# Arduino_Nanolu_Kart_2.net
KiCad netlist of a schematic drawn in EAGLE
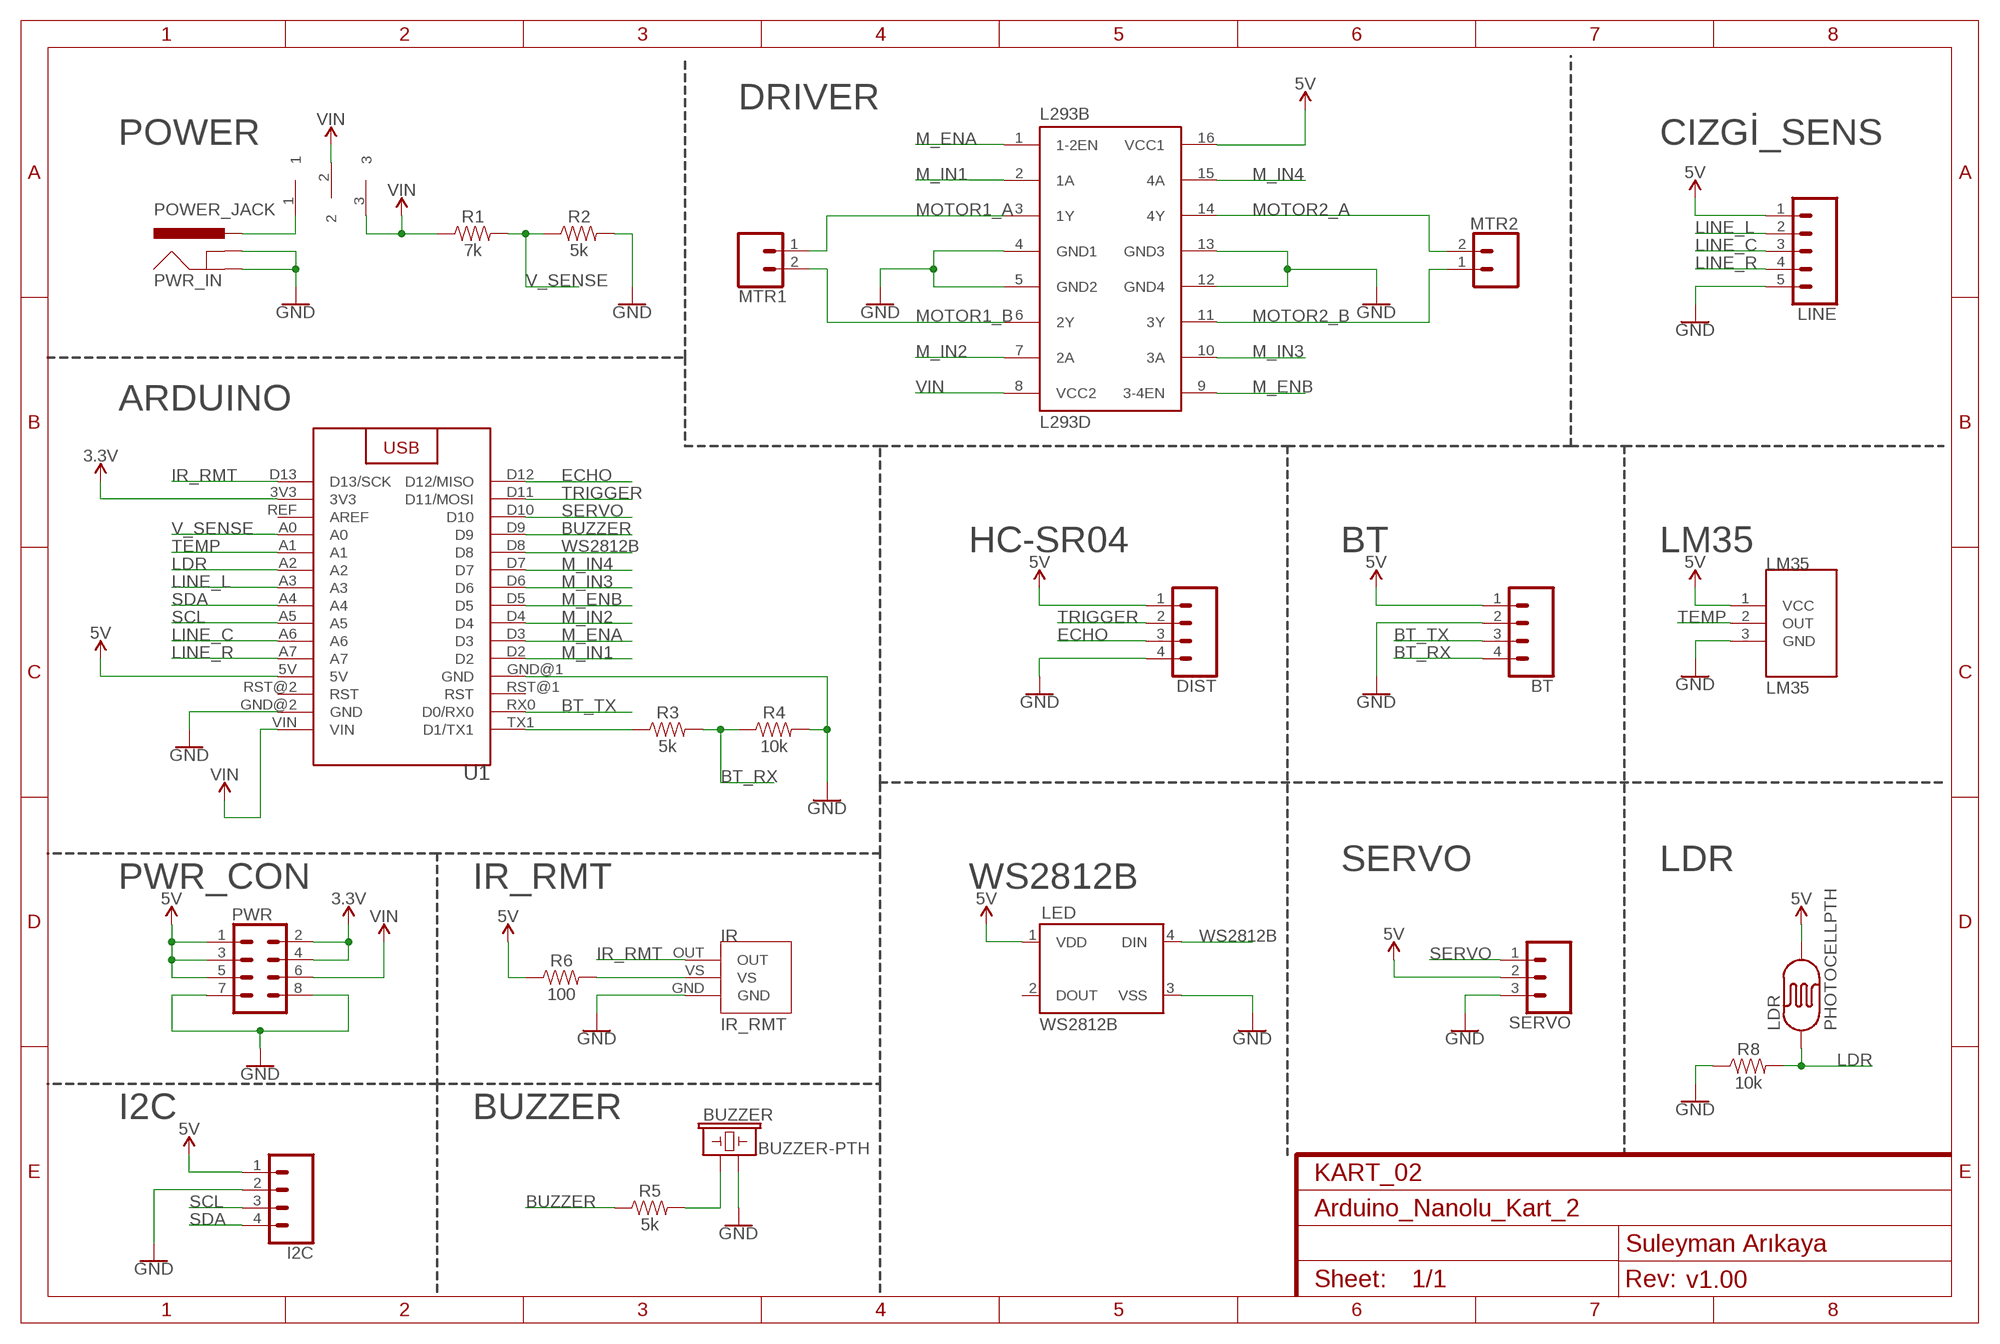
[diagram p0: schematic, sheet 1]

(export (version "E")
  (design (tool "Eeschema 10.0.6"))
  (components
    (comp (ref "BT")
      (value "CONN_04")
      (footprint "eagle-import:1X04")
      (libsource (lib "eagle-import") (part "CONN_04"))
    )
    (comp (ref "BUZZER")
      (value "BUZZER-PTH")
      (footprint "eagle-import:BUZZER-12MM")
      (libsource (lib "eagle-import") (part "BUZZER-PTH"))
    )
    (comp (ref "DIST")
      (value "CONN_04")
      (footprint "eagle-import:1X04")
      (libsource (lib "eagle-import") (part "CONN_04"))
    )
    (comp (ref "I2C")
      (value "CONN_04")
      (footprint "eagle-import:1X04")
      (libsource (lib "eagle-import") (part "CONN_04"))
    )
    (comp (ref "IR")
      (value "IR_RMT")
      (footprint "eagle-import:IR_SENSOR")
      (libsource (lib "eagle-import") (part "IR_SENSOR"))
    )
    (comp (ref "L293B")
      (value "L293D")
      (footprint "eagle-import:DIL16")
      (libsource (lib "eagle-import") (part "L293D"))
    )
    (comp (ref "LDR")
      (value "PHOTOCELLPTH")
      (footprint "eagle-import:PHOTOCELL")
      (libsource (lib "eagle-import") (part "PHOTOCELLPTH"))
    )
    (comp (ref "LED")
      (value "WS2812B")
      (footprint "eagle-import:WS2812B")
      (libsource (lib "eagle-import") (part "WS2812B"))
    )
    (comp (ref "LINE")
      (value "CONN_05")
      (footprint "eagle-import:1X05")
      (libsource (lib "eagle-import") (part "CONN_05"))
    )
    (comp (ref "LM35")
      (value "LM35")
      (footprint "eagle-import:TO-92")
      (fields (field (name "SPICEPREFIX") "U"))
      (libsource (lib "eagle-import") (part "LM35"))
    )
    (comp (ref "MTR1")
      (value "CONN_023.5MM")
      (footprint "eagle-import:SCREWTERMINAL-3.5MM-2")
      (libsource (lib "eagle-import") (part "CONN_023.5MM"))
    )
    (comp (ref "MTR2")
      (value "CONN_023.5MM")
      (footprint "eagle-import:SCREWTERMINAL-3.5MM-2")
      (libsource (lib "eagle-import") (part "CONN_023.5MM"))
    )
    (comp (ref "PWR")
      (value "CONN_04X2")
      (footprint "eagle-import:2X4")
      (libsource (lib "eagle-import") (part "CONN_04X2"))
    )
    (comp (ref "PWR_IN")
      (value "POWER_JACK")
      (footprint "eagle-import:POWER_JACK_PTH")
      (libsource (lib "eagle-import") (part "POWER_JACK"))
    )
    (comp (ref "R1")
      (value "7k")
      (footprint "eagle-import:AXIAL-0.3")
      (libsource (lib "eagle-import") (part "1KOHM-HORIZ-1/4W-5%"))
    )
    (comp (ref "R2")
      (value "5k")
      (footprint "eagle-import:AXIAL-0.3")
      (libsource (lib "eagle-import") (part "1KOHM-HORIZ-1/4W-5%"))
    )
    (comp (ref "R3")
      (value "5k")
      (footprint "eagle-import:AXIAL-0.3")
      (libsource (lib "eagle-import") (part "1KOHM-HORIZ-1/4W-5%"))
    )
    (comp (ref "R4")
      (value "10k")
      (footprint "eagle-import:AXIAL-0.3")
      (libsource (lib "eagle-import") (part "1KOHM-HORIZ-1/4W-5%"))
    )
    (comp (ref "R5")
      (value "5k")
      (footprint "eagle-import:AXIAL-0.3")
      (libsource (lib "eagle-import") (part "1KOHM-HORIZ-1/4W-5%"))
    )
    (comp (ref "R6")
      (value "100")
      (footprint "eagle-import:AXIAL-0.3")
      (libsource (lib "eagle-import") (part "1KOHM-HORIZ-1/4W-5%"))
    )
    (comp (ref "R8")
      (value "10k")
      (footprint "eagle-import:AXIAL-0.3")
      (libsource (lib "eagle-import") (part "1KOHM-HORIZ-1/4W-5%"))
    )
    (comp (ref "SERVO")
      (value "CONN_03")
      (footprint "eagle-import:1X03")
      (libsource (lib "eagle-import") (part "CONN_03"))
    )
    (comp (ref "SWICH")
      (value "SWICH_X2_3MM")
      (footprint "eagle-import:SWICH_X2_3MM")
      (libsource (lib "eagle-import") (part "SWICH_X2_3MM"))
    )
    (comp (ref "U1")
      (value "ARDUINO_NANO")
      (footprint "eagle-import:ARDUINO_NANO")
      (libsource (lib "eagle-import") (part "ARDUINO_NANO"))
    )
  )
  (nets
    (net (code "1") (name "/BT_RX") (class "Default")
      (node (ref "BT") (pin "4") (pinfunction "4_4") (pintype "passive"))
      (node (ref "R3") (pin "P$2") (pinfunction "2_P$2") (pintype "passive"))
      (node (ref "R4") (pin "P$1") (pinfunction "1_P$1") (pintype "passive"))
    )
    (net (code "2") (name "/BT_TX") (class "Default")
      (node (ref "BT") (pin "3") (pinfunction "3_3") (pintype "passive"))
      (node (ref "U1") (pin "RX0") (pinfunction "D0/RX0_RX0") (pintype "bidirectional"))
    )
    (net (code "3") (name "/BUZZER") (class "Default")
      (node (ref "R5") (pin "P$1") (pinfunction "1_P$1") (pintype "passive"))
      (node (ref "U1") (pin "D9") (pinfunction "D9_D9") (pintype "bidirectional"))
    )
    (net (code "4") (name "/ECHO") (class "Default")
      (node (ref "DIST") (pin "3") (pinfunction "3_3") (pintype "passive"))
      (node (ref "U1") (pin "D12") (pinfunction "D12/MISO_D12") (pintype "bidirectional"))
    )
    (net (code "5") (name "/IR_RMT") (class "Default")
      (node (ref "IR") (pin "OUT") (pinfunction "OUT_OUT") (pintype "bidirectional"))
      (node (ref "U1") (pin "D13") (pinfunction "D13/SCK_D13") (pintype "bidirectional"))
    )
    (net (code "6") (name "/LDR") (class "Default")
      (node (ref "LDR") (pin "1") (pinfunction "P$1_1") (pintype "bidirectional"))
      (node (ref "R8") (pin "P$2") (pinfunction "2_P$2") (pintype "passive"))
      (node (ref "U1") (pin "A2") (pinfunction "A2_A2") (pintype "bidirectional"))
    )
    (net (code "7") (name "/LINE_C") (class "Default")
      (node (ref "LINE") (pin "3") (pinfunction "3_3") (pintype "passive"))
      (node (ref "U1") (pin "A6") (pinfunction "A6_A6") (pintype "bidirectional"))
    )
    (net (code "8") (name "/LINE_L") (class "Default")
      (node (ref "LINE") (pin "2") (pinfunction "2_2") (pintype "passive"))
      (node (ref "U1") (pin "A3") (pinfunction "A3_A3") (pintype "bidirectional"))
    )
    (net (code "9") (name "/LINE_R") (class "Default")
      (node (ref "LINE") (pin "4") (pinfunction "4_4") (pintype "passive"))
      (node (ref "U1") (pin "A7") (pinfunction "A7_A7") (pintype "bidirectional"))
    )
    (net (code "10") (name "/MOTOR1_A") (class "Default")
      (node (ref "L293B") (pin "3") (pinfunction "1Y_3") (pintype "output"))
      (node (ref "MTR1") (pin "1") (pinfunction "1_1") (pintype "passive"))
    )
    (net (code "11") (name "/MOTOR1_B") (class "Default")
      (node (ref "L293B") (pin "6") (pinfunction "2Y_6") (pintype "output"))
      (node (ref "MTR1") (pin "2") (pinfunction "2_2") (pintype "passive"))
    )
    (net (code "12") (name "/MOTOR2_A") (class "Default")
      (node (ref "L293B") (pin "14") (pinfunction "4Y_14") (pintype "output"))
      (node (ref "MTR2") (pin "2") (pinfunction "2_2") (pintype "passive"))
    )
    (net (code "13") (name "/MOTOR2_B") (class "Default")
      (node (ref "L293B") (pin "11") (pinfunction "3Y_11") (pintype "output"))
      (node (ref "MTR2") (pin "1") (pinfunction "1_1") (pintype "passive"))
    )
    (net (code "14") (name "/M_ENA") (class "Default")
      (node (ref "L293B") (pin "1") (pinfunction "1-2EN_1") (pintype "input"))
      (node (ref "U1") (pin "D3") (pinfunction "D3_D3") (pintype "bidirectional"))
    )
    (net (code "15") (name "/M_ENB") (class "Default")
      (node (ref "L293B") (pin "9") (pinfunction "3-4EN_9") (pintype "input"))
      (node (ref "U1") (pin "D5") (pinfunction "D5_D5") (pintype "bidirectional"))
    )
    (net (code "16") (name "/M_IN1") (class "Default")
      (node (ref "L293B") (pin "2") (pinfunction "1A_2") (pintype "input"))
      (node (ref "U1") (pin "D2") (pinfunction "D2_D2") (pintype "bidirectional"))
    )
    (net (code "17") (name "/M_IN2") (class "Default")
      (node (ref "L293B") (pin "7") (pinfunction "2A_7") (pintype "input"))
      (node (ref "U1") (pin "D4") (pinfunction "D4_D4") (pintype "bidirectional"))
    )
    (net (code "18") (name "/M_IN3") (class "Default")
      (node (ref "L293B") (pin "10") (pinfunction "3A_10") (pintype "input"))
      (node (ref "U1") (pin "D6") (pinfunction "D6_D6") (pintype "bidirectional"))
    )
    (net (code "19") (name "/M_IN4") (class "Default")
      (node (ref "L293B") (pin "15") (pinfunction "4A_15") (pintype "input"))
      (node (ref "U1") (pin "D7") (pinfunction "D7_D7") (pintype "bidirectional"))
    )
    (net (code "20") (name "/SCL") (class "Default")
      (node (ref "I2C") (pin "3") (pinfunction "3_3") (pintype "passive"))
      (node (ref "U1") (pin "A5") (pinfunction "A5_A5") (pintype "bidirectional"))
    )
    (net (code "21") (name "/SDA") (class "Default")
      (node (ref "I2C") (pin "4") (pinfunction "4_4") (pintype "passive"))
      (node (ref "U1") (pin "A4") (pinfunction "A4_A4") (pintype "bidirectional"))
    )
    (net (code "22") (name "/SERVO") (class "Default")
      (node (ref "SERVO") (pin "1") (pinfunction "1_1") (pintype "passive"))
      (node (ref "U1") (pin "D10") (pinfunction "D10_D10") (pintype "bidirectional"))
    )
    (net (code "23") (name "/TEMP") (class "Default")
      (node (ref "LM35") (pin "2") (pinfunction "OUT_2") (pintype "bidirectional"))
      (node (ref "U1") (pin "A1") (pinfunction "A1_A1") (pintype "bidirectional"))
    )
    (net (code "24") (name "/TRIGGER") (class "Default")
      (node (ref "DIST") (pin "2") (pinfunction "2_2") (pintype "passive"))
      (node (ref "U1") (pin "D11") (pinfunction "D11/MOSI_D11") (pintype "bidirectional"))
    )
    (net (code "25") (name "/V_SENSE") (class "Default")
      (node (ref "R1") (pin "P$2") (pinfunction "2_P$2") (pintype "passive"))
      (node (ref "R2") (pin "P$1") (pinfunction "1_P$1") (pintype "passive"))
      (node (ref "U1") (pin "A0") (pinfunction "A0_A0") (pintype "bidirectional"))
    )
    (net (code "26") (name "/WS2812B") (class "Default")
      (node (ref "LED") (pin "4") (pinfunction "DIN_4") (pintype "input"))
      (node (ref "U1") (pin "D8") (pinfunction "D8_D8") (pintype "bidirectional"))
    )
    (net (code "27") (name "3.3V") (class "Default")
      (node (ref "PWR") (pin "2") (pinfunction "2_2") (pintype "passive"))
      (node (ref "PWR") (pin "4") (pinfunction "4_4") (pintype "passive"))
      (node (ref "U1") (pin "3V3") (pinfunction "3V3_3V3") (pintype "bidirectional"))
    )
    (net (code "28") (name "5V") (class "Default")
      (node (ref "BT") (pin "1") (pinfunction "1_1") (pintype "passive"))
      (node (ref "DIST") (pin "1") (pinfunction "1_1") (pintype "passive"))
      (node (ref "I2C") (pin "1") (pinfunction "1_1") (pintype "passive"))
      (node (ref "L293B") (pin "16") (pinfunction "VCC1_16") (pintype "power_in"))
      (node (ref "LDR") (pin "2") (pinfunction "P$2_2") (pintype "bidirectional"))
      (node (ref "LED") (pin "1") (pinfunction "VDD_1") (pintype "power_in"))
      (node (ref "LINE") (pin "1") (pinfunction "1_1") (pintype "passive"))
      (node (ref "LM35") (pin "1") (pinfunction "VCC_1") (pintype "bidirectional"))
      (node (ref "PWR") (pin "1") (pinfunction "1_1") (pintype "passive"))
      (node (ref "PWR") (pin "3") (pinfunction "3_3") (pintype "passive"))
      (node (ref "PWR") (pin "5") (pinfunction "5_5") (pintype "passive"))
      (node (ref "R6") (pin "P$1") (pinfunction "1_P$1") (pintype "passive"))
      (node (ref "SERVO") (pin "2") (pinfunction "2_2") (pintype "passive"))
      (node (ref "U1") (pin "5V") (pinfunction "5V_5V") (pintype "bidirectional"))
    )
    (net (code "29") (name "GND") (class "Default")
      (node (ref "BT") (pin "2") (pinfunction "2_2") (pintype "passive"))
      (node (ref "BUZZER") (pin "-") (pinfunction "2_-") (pintype "passive"))
      (node (ref "DIST") (pin "4") (pinfunction "4_4") (pintype "passive"))
      (node (ref "I2C") (pin "2") (pinfunction "2_2") (pintype "passive"))
      (node (ref "IR") (pin "GND") (pinfunction "GND_GND") (pintype "bidirectional"))
      (node (ref "L293B") (pin "12") (pinfunction "GND4_12") (pintype "power_in"))
      (node (ref "L293B") (pin "13") (pinfunction "GND3_13") (pintype "power_in"))
      (node (ref "L293B") (pin "4") (pinfunction "GND1_4") (pintype "power_in"))
      (node (ref "L293B") (pin "5") (pinfunction "GND2_5") (pintype "power_in"))
      (node (ref "LED") (pin "3") (pinfunction "VSS_3") (pintype "power_in"))
      (node (ref "LINE") (pin "5") (pinfunction "5_5") (pintype "passive"))
      (node (ref "LM35") (pin "3") (pinfunction "GND_3") (pintype "bidirectional"))
      (node (ref "PWR") (pin "7") (pinfunction "7_7") (pintype "passive"))
      (node (ref "PWR") (pin "8") (pinfunction "8_8") (pintype "passive"))
      (node (ref "PWR_IN") (pin "GND") (pinfunction "GND_GND") (pintype "bidirectional"))
      (node (ref "PWR_IN") (pin "GNDBREAK") (pinfunction "GNDBREAK_GNDBREAK") (pintype "bidirectional"))
      (node (ref "R2") (pin "P$2") (pinfunction "2_P$2") (pintype "passive"))
      (node (ref "R4") (pin "P$2") (pinfunction "2_P$2") (pintype "passive"))
      (node (ref "R8") (pin "P$1") (pinfunction "1_P$1") (pintype "passive"))
      (node (ref "SERVO") (pin "3") (pinfunction "3_3") (pintype "passive"))
      (node (ref "U1") (pin "GND@1") (pinfunction "GND_GND@1") (pintype "bidirectional"))
      (node (ref "U1") (pin "GND@2") (pinfunction "GND_GND@2") (pintype "bidirectional"))
    )
    (net (code "30") (name "Net-(BUZZER-1)") (class "Default")
      (node (ref "BUZZER") (pin "+") (pinfunction "1_+") (pintype "passive"))
      (node (ref "R5") (pin "P$2") (pinfunction "2_P$2") (pintype "passive"))
    )
    (net (code "31") (name "Net-(PWR_IN-PadPWR)") (class "Default")
      (node (ref "PWR_IN") (pin "PWR") (pinfunction "PWR_PWR") (pintype "bidirectional"))
      (node (ref "SWICH") (pin "1") (pinfunction "1_1") (pintype "bidirectional"))
    )
    (net (code "32") (name "Net-(R3-1)") (class "Default")
      (node (ref "R3") (pin "P$1") (pinfunction "1_P$1") (pintype "passive"))
      (node (ref "U1") (pin "TX1") (pinfunction "D1/TX1_TX1") (pintype "bidirectional"))
    )
    (net (code "33") (name "Net-(R6-2)") (class "Default")
      (node (ref "IR") (pin "VS") (pinfunction "VS_VS") (pintype "bidirectional"))
      (node (ref "R6") (pin "P$2") (pinfunction "2_P$2") (pintype "passive"))
    )
    (net (code "34") (name "VIN") (class "Default")
      (node (ref "L293B") (pin "8") (pinfunction "VCC2_8") (pintype "power_in"))
      (node (ref "PWR") (pin "6") (pinfunction "6_6") (pintype "passive"))
      (node (ref "R1") (pin "P$1") (pinfunction "1_P$1") (pintype "passive"))
      (node (ref "SWICH") (pin "2") (pinfunction "2_2") (pintype "bidirectional"))
      (node (ref "SWICH") (pin "3") (pinfunction "3_3") (pintype "bidirectional"))
      (node (ref "U1") (pin "VIN") (pinfunction "VIN_VIN") (pintype "bidirectional"))
    )
    (net (code "35") (name "unconnected-(LED-DOUT-Pad2)") (class "Default")
      (node (ref "LED") (pin "2") (pinfunction "DOUT_2") (pintype "output"))
    )
    (net (code "36") (name "unconnected-(U1-AREF-PadREF)") (class "Default")
      (node (ref "U1") (pin "REF") (pinfunction "AREF_REF") (pintype "bidirectional"))
    )
    (net (code "37") (name "unconnected-(U1-RST-PadRST@1)") (class "Default")
      (node (ref "U1") (pin "RST@1") (pinfunction "RST_RST@1") (pintype "bidirectional"))
    )
    (net (code "38") (name "unconnected-(U1-RST-PadRST@2)") (class "Default")
      (node (ref "U1") (pin "RST@2") (pinfunction "RST_RST@2") (pintype "bidirectional"))
    )
  )
)
